# AdditionalSensor.net
KiCad netlist of a schematic drawn in EAGLE
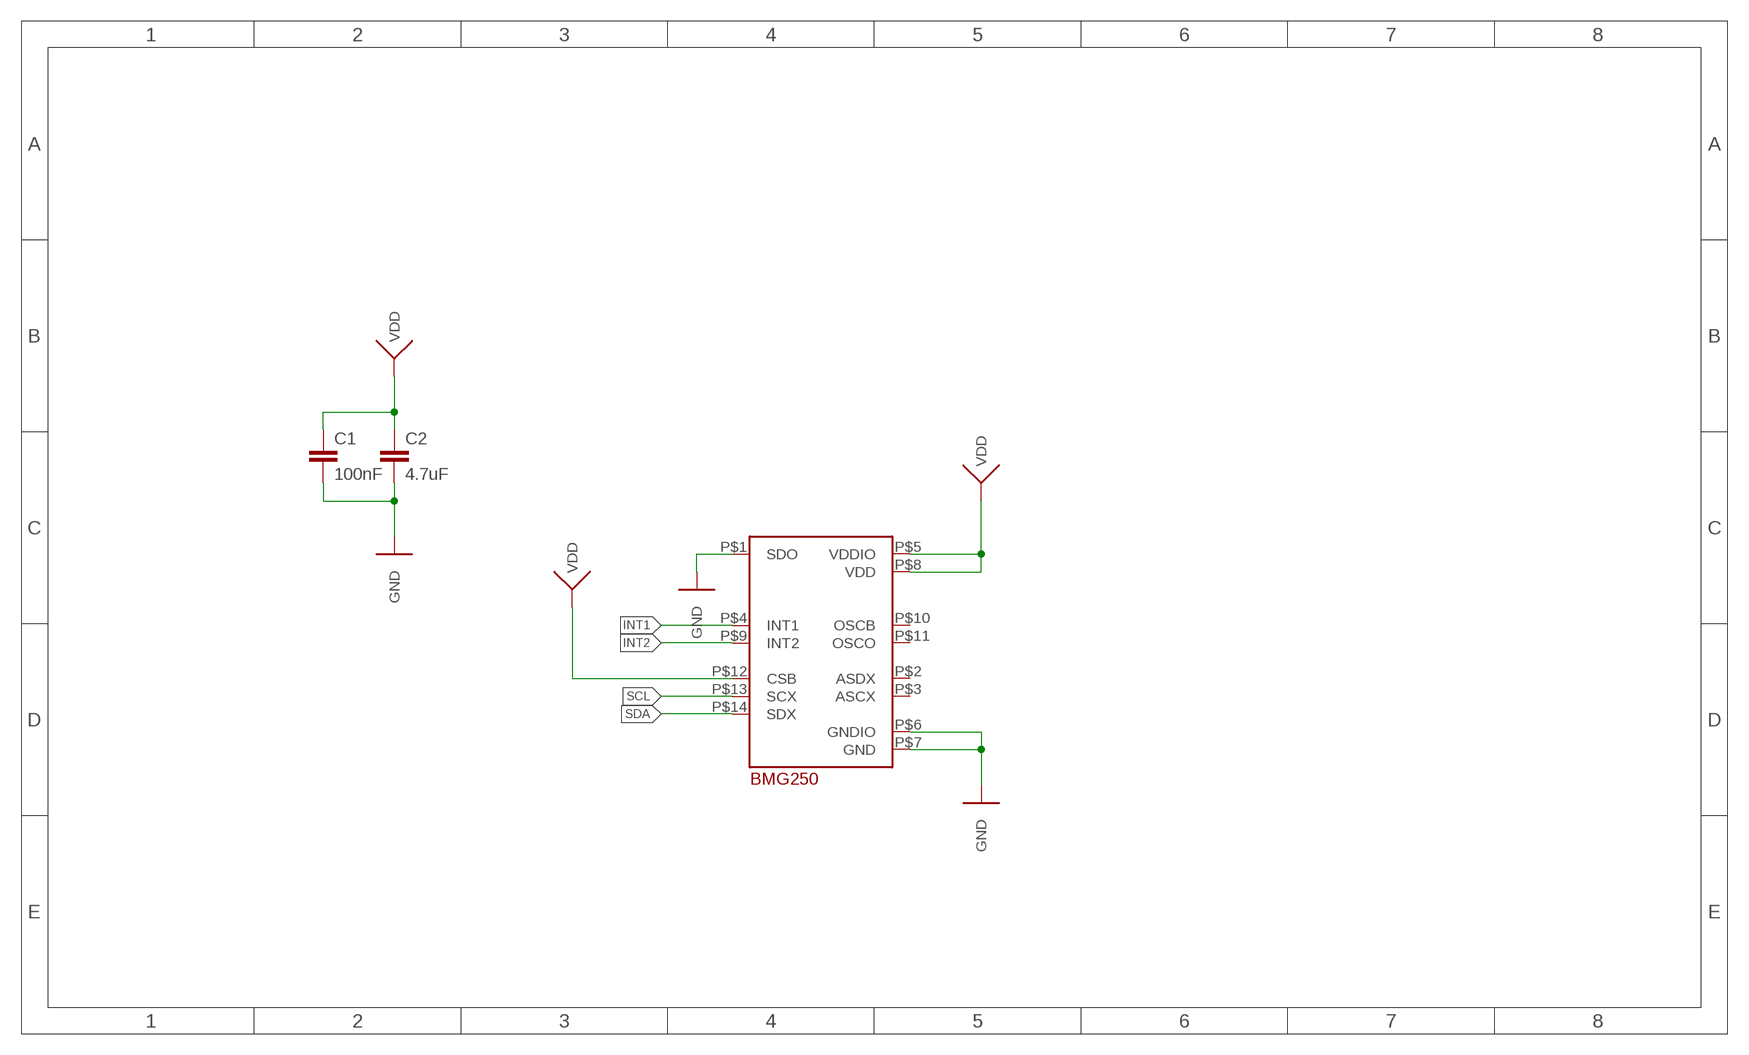
[diagram p0: schematic, sheet 1]

(export (version "E")
  (design (tool "Eeschema 10.0.6"))
  (components
    (comp (ref "C1")
      (value "100nF")
      (footprint "eagle-import:C0603")
      (libsource (lib "eagle-import") (part "CAPACITOR0603"))
    )
    (comp (ref "C2")
      (value "4.7uF")
      (footprint "eagle-import:C0603")
      (libsource (lib "eagle-import") (part "CAPACITOR0603"))
    )
    (comp (ref "U1")
      (value "BMG250")
      (footprint "eagle-import:LGA14")
      (libsource (lib "eagle-import") (part "BMG250"))
    )
  )
  (nets
    (net (code "1") (name "GND") (class "Default")
      (node (ref "C1") (pin "2") (pinfunction "2_2") (pintype "passive"))
      (node (ref "C2") (pin "2") (pinfunction "2_2") (pintype "passive"))
      (node (ref "U1") (pin "P$1") (pinfunction "SDO_P$1") (pintype "bidirectional"))
      (node (ref "U1") (pin "P$6") (pinfunction "GNDIO_P$6") (pintype "power_in"))
      (node (ref "U1") (pin "P$7") (pinfunction "GND_P$7") (pintype "power_in"))
    )
    (net (code "2") (name "INT1") (class "Default")
      (node (ref "U1") (pin "P$4") (pinfunction "INT1_P$4") (pintype "bidirectional"))
    )
    (net (code "3") (name "INT2") (class "Default")
      (node (ref "U1") (pin "P$9") (pinfunction "INT2_P$9") (pintype "bidirectional"))
    )
    (net (code "4") (name "SCL") (class "Default")
      (node (ref "U1") (pin "P$13") (pinfunction "SCX_P$13") (pintype "bidirectional"))
    )
    (net (code "5") (name "SDA") (class "Default")
      (node (ref "U1") (pin "P$14") (pinfunction "SDX_P$14") (pintype "bidirectional"))
    )
    (net (code "6") (name "VDD") (class "Default")
      (node (ref "C1") (pin "1") (pinfunction "1_1") (pintype "passive"))
      (node (ref "C2") (pin "1") (pinfunction "1_1") (pintype "passive"))
      (node (ref "U1") (pin "P$12") (pinfunction "CSB_P$12") (pintype "bidirectional"))
      (node (ref "U1") (pin "P$5") (pinfunction "VDDIO_P$5") (pintype "power_in"))
      (node (ref "U1") (pin "P$8") (pinfunction "VDD_P$8") (pintype "power_in"))
    )
    (net (code "7") (name "unconnected-(U1-ASCX-PadP$3)") (class "Default")
      (node (ref "U1") (pin "P$3") (pinfunction "ASCX_P$3") (pintype "bidirectional"))
    )
    (net (code "8") (name "unconnected-(U1-ASDX-PadP$2)") (class "Default")
      (node (ref "U1") (pin "P$2") (pinfunction "ASDX_P$2") (pintype "bidirectional"))
    )
    (net (code "9") (name "unconnected-(U1-OSCB-PadP$10)") (class "Default")
      (node (ref "U1") (pin "P$10") (pinfunction "OSCB_P$10") (pintype "bidirectional"))
    )
    (net (code "10") (name "unconnected-(U1-OSCO-PadP$11)") (class "Default")
      (node (ref "U1") (pin "P$11") (pinfunction "OSCO_P$11") (pintype "bidirectional"))
    )
  )
)
